# HHOLowCost.net
KiCad netlist of a schematic drawn in Altium Designer
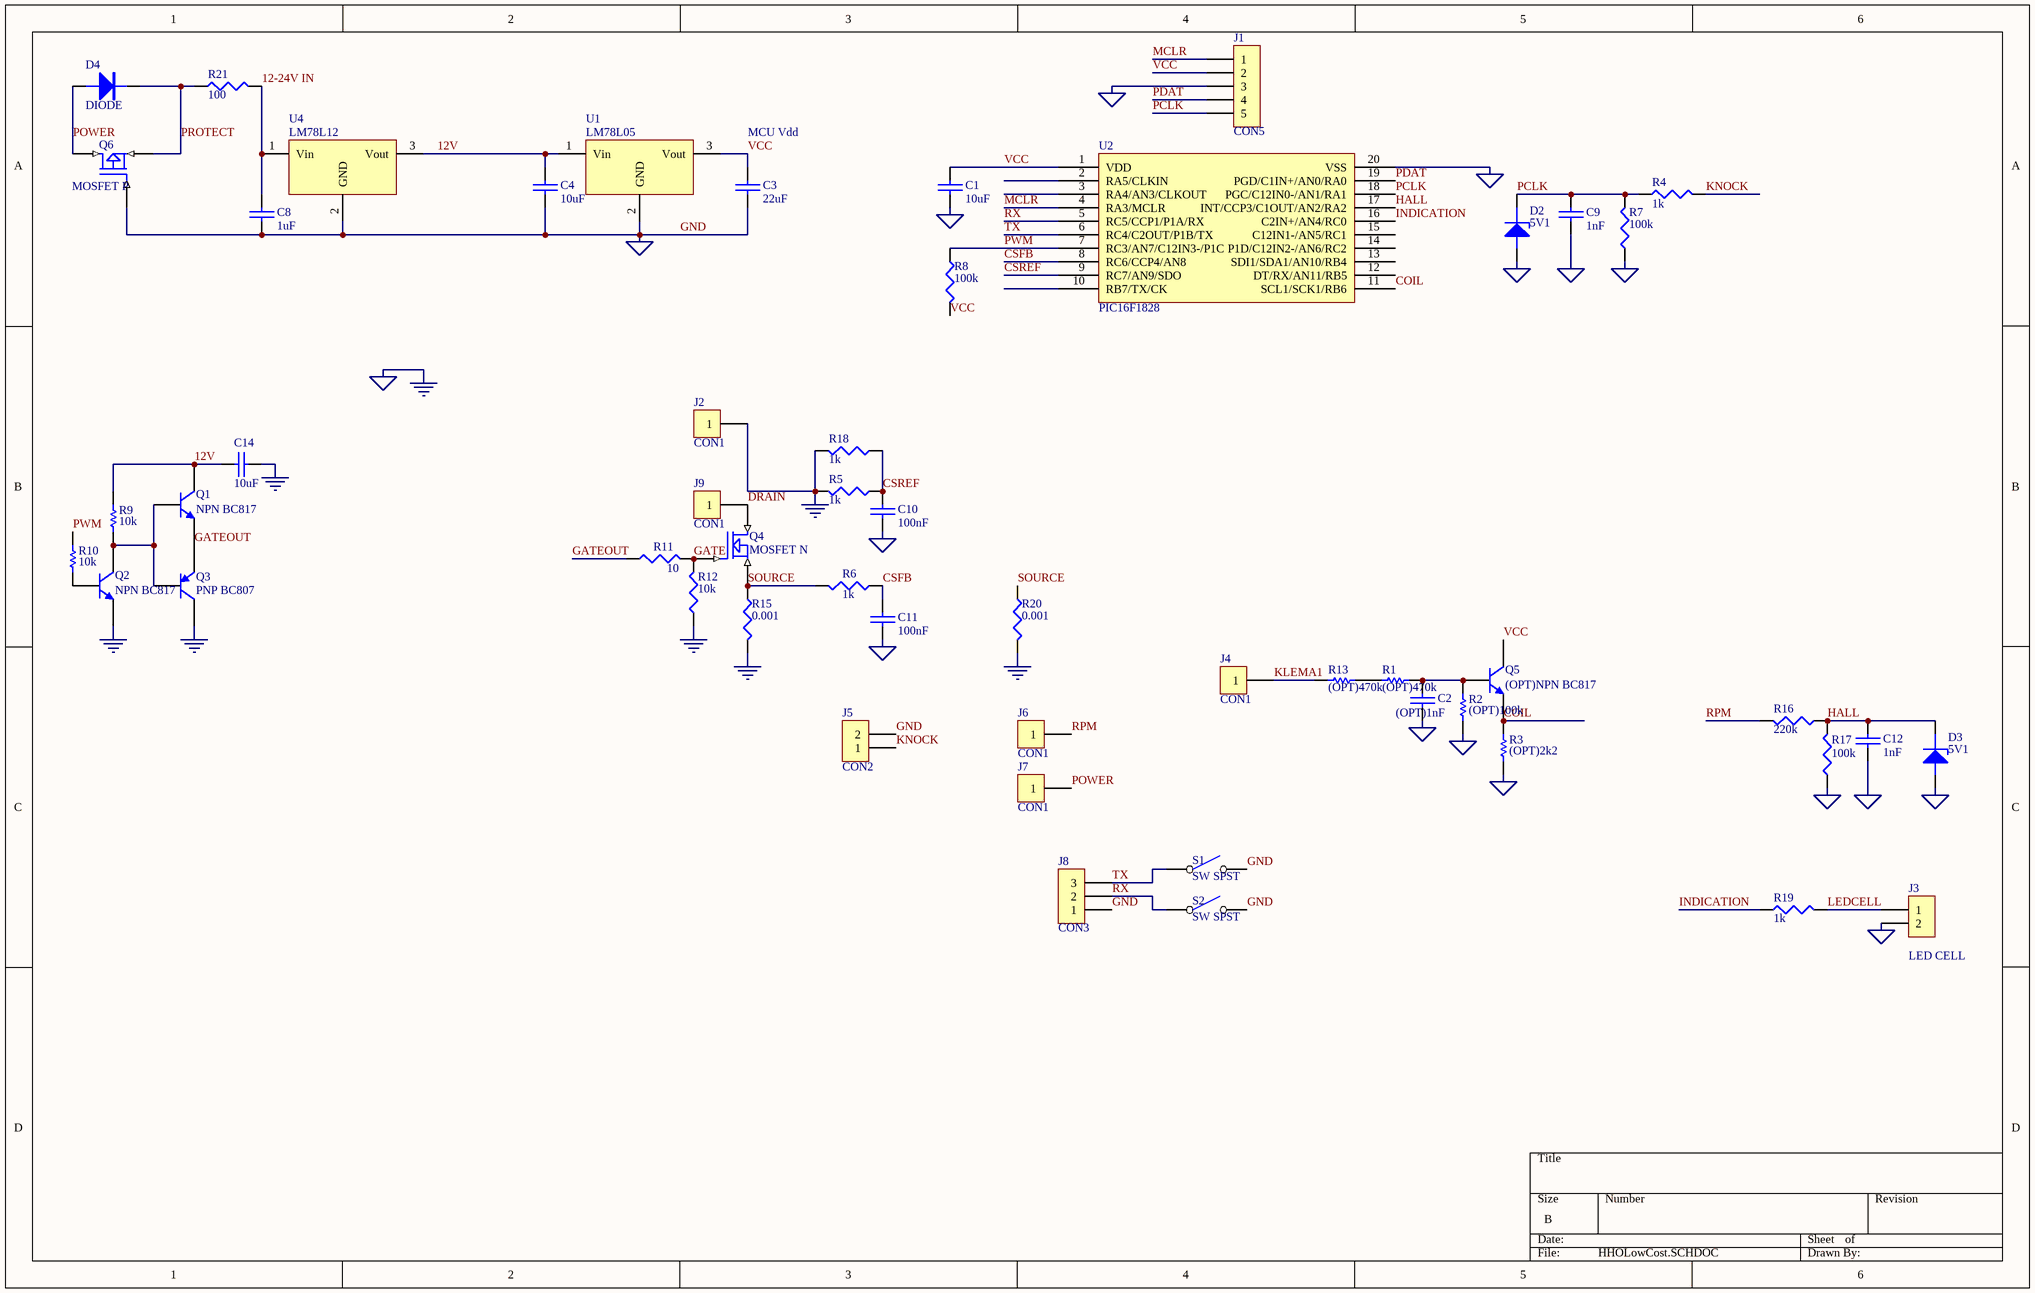
[diagram p0: HHOLowCost.SCHDOC]

(export (version "E")
  (design (tool "Eeschema 10.0.6"))
  (components
    (comp (ref "C1")
      (value "10uF")
      (footprint "0805")
      (description "Capacitor")
      (libsource (lib "*") (part "CAP"))
    )
    (comp (ref "C2")
      (value "(OPT)1nF")
      (footprint "0603 CAP")
      (description "Capacitor")
      (libsource (lib "*") (part "CAP"))
    )
    (comp (ref "C3")
      (value "22uF")
      (footprint "0805")
      (description "Capacitor")
      (libsource (lib "*") (part "CAP"))
    )
    (comp (ref "C4")
      (value "10uF")
      (footprint "0805")
      (description "Capacitor")
      (libsource (lib "*") (part "CAP"))
    )
    (comp (ref "C8")
      (value "1uF")
      (footprint "0805")
      (description "Capacitor")
      (libsource (lib "*") (part "CAP"))
    )
    (comp (ref "C9")
      (value "1nF")
      (footprint "0603 CAP")
      (description "Capacitor")
      (libsource (lib "*") (part "CAP"))
    )
    (comp (ref "C10")
      (value "100nF")
      (footprint "0603 CAP")
      (description "Capacitor")
      (libsource (lib "*") (part "CAP"))
    )
    (comp (ref "C11")
      (value "100nF")
      (footprint "0603 CAP")
      (description "Capacitor")
      (libsource (lib "*") (part "CAP"))
    )
    (comp (ref "C12")
      (value "1nF")
      (footprint "0603 CAP")
      (description "Capacitor")
      (libsource (lib "*") (part "CAP"))
    )
    (comp (ref "C14")
      (value "10uF")
      (footprint "0805")
      (description "Capacitor")
      (libsource (lib "*") (part "CAP"))
    )
    (comp (ref "D2")
      (value "5V1")
      (footprint "SOT-23 2 PIN")
      (description "Zener Diode")
      (libsource (lib "Miscellaneous Devices") (part "ZENER1"))
    )
    (comp (ref "D3")
      (value "5V1")
      (footprint "SOT-23 2 PIN")
      (description "Zener Diode")
      (libsource (lib "Miscellaneous Devices") (part "ZENER1"))
    )
    (comp (ref "D4")
      (value "DIODE")
      (footprint "SMA + SOT23")
      (description "Diode")
      (libsource (lib "Miscellaneous Devices") (part "DIODE"))
    )
    (comp (ref "J1")
      (value "CON5")
      (footprint "SIP5 - PGM")
      (description "Connector")
      (libsource (lib "Miscellaneous Devices") (part "CON5"))
    )
    (comp (ref "J2")
      (value "CON1")
      (footprint "HD 11mm 1P")
      (description "Connector")
      (libsource (lib "Miscellaneous Devices") (part "CON1"))
    )
    (comp (ref "J3")
      (value "LED CELL")
      (footprint "SIP2")
      (description "Connector")
      (libsource (lib "Miscellaneous Devices") (part "CON2"))
    )
    (comp (ref "J4")
      (value "CON1")
      (footprint "HD-351 1P")
      (description "Connector")
      (libsource (lib "Miscellaneous Devices") (part "CON1"))
    )
    (comp (ref "J5")
      (value "CON2")
      (footprint "HD-351 2P")
      (description "Connector")
      (libsource (lib "") (part "CON2_1"))
    )
    (comp (ref "J6")
      (value "CON1")
      (footprint "HD-351 1P")
      (description "Connector")
      (libsource (lib "Miscellaneous Devices") (part "CON1"))
    )
    (comp (ref "J7")
      (value "CON1")
      (footprint "HD-351 1P")
      (description "Connector")
      (libsource (lib "Miscellaneous Devices") (part "CON1"))
    )
    (comp (ref "J8")
      (value "CON3")
      (footprint "SIP3")
      (description "Connector")
      (libsource (lib "Miscellaneous Devices") (part "CON3"))
    )
    (comp (ref "J9")
      (value "CON1")
      (footprint "HD 11mm 1P")
      (description "Connector")
      (libsource (lib "Miscellaneous Devices") (part "CON1"))
    )
    (comp (ref "Q1")
      (value "NPN BC817")
      (footprint "SOT-23")
      (description "NPN Bipolar Transistor")
      (fields
        (field (name "MANUFACTURER") "Generic Components")
        (field (name "PUBLISHER") "Altium Hobart Technology Centre")
      )
      (libsource (lib "Miscellaneous Devices") (part "NPN"))
    )
    (comp (ref "Q2")
      (value "NPN BC817")
      (footprint "SOT-23")
      (description "NPN Bipolar Transistor")
      (fields
        (field (name "MANUFACTURER") "Generic Components")
        (field (name "PUBLISHER") "Altium Hobart Technology Centre")
      )
      (libsource (lib "Miscellaneous Devices") (part "NPN"))
    )
    (comp (ref "Q3")
      (value "PNP BC807")
      (footprint "sot-23")
      (description "PNP Bipolar Transistor")
      (fields
        (field (name "MANUFACTURER") "Generic Components")
        (field (name "PUBLISHER") "Altium Hobart Technology Centre")
      )
      (libsource (lib "Miscellaneous Devices") (part "PNP"))
    )
    (comp (ref "Q4")
      (value "MOSFET N")
      (footprint "D2-Pack - 7")
      (libsource (lib "Miscellaneous Devices") (part "MOSFET N"))
    )
    (comp (ref "Q5")
      (value "(OPT)NPN BC817")
      (footprint "SOT-23")
      (description "NPN Bipolar Transistor")
      (fields
        (field (name "MANUFACTURER") "Generic Components")
        (field (name "PUBLISHER") "Altium Hobart Technology Centre")
      )
      (libsource (lib "Miscellaneous Devices") (part "NPN"))
    )
    (comp (ref "Q6")
      (value "MOSFET P")
      (footprint "SOT-23")
      (libsource (lib "Miscellaneous Devices") (part "MOSFET P"))
    )
    (comp (ref "R1")
      (value "(OPT)470k")
      (footprint "0805")
      (description "Resistor")
      (fields
        (field (name "MANUFACTURER") "Generic Components")
        (field (name "PUBLISHER") "Altium Hobart Technology Centre")
      )
      (libsource (lib "Miscellaneous Devices") (part "Res1"))
    )
    (comp (ref "R2")
      (value "(OPT)100k")
      (footprint "0603")
      (description "Resistor")
      (fields
        (field (name "MANUFACTURER") "Generic Components")
        (field (name "PUBLISHER") "Altium Hobart Technology Centre")
      )
      (libsource (lib "Miscellaneous Devices") (part "Res1"))
    )
    (comp (ref "R3")
      (value "(OPT)2k2")
      (footprint "0603")
      (description "Resistor")
      (fields
        (field (name "MANUFACTURER") "Generic Components")
        (field (name "PUBLISHER") "Altium Hobart Technology Centre")
      )
      (libsource (lib "Miscellaneous Devices") (part "Res1"))
    )
    (comp (ref "R4")
      (value "1k")
      (footprint "0603 RES")
      (libsource (lib "Miscellaneous Devices") (part "RES1"))
    )
    (comp (ref "R5")
      (value "1k")
      (footprint "0603 RES")
      (libsource (lib "Miscellaneous Devices") (part "RES1"))
    )
    (comp (ref "R6")
      (value "1k")
      (footprint "0603 RES")
      (libsource (lib "Miscellaneous Devices") (part "RES1"))
    )
    (comp (ref "R7")
      (value "100k")
      (footprint "0603 RES")
      (libsource (lib "Miscellaneous Devices") (part "RES1"))
    )
    (comp (ref "R8")
      (value "100k")
      (footprint "0603 RES")
      (libsource (lib "Miscellaneous Devices") (part "RES1"))
    )
    (comp (ref "R9")
      (value "10k")
      (footprint "0603")
      (description "Resistor")
      (fields
        (field (name "MANUFACTURER") "Generic Components")
        (field (name "PUBLISHER") "Altium Hobart Technology Centre")
      )
      (libsource (lib "Miscellaneous Devices") (part "Res1"))
    )
    (comp (ref "R10")
      (value "10k")
      (footprint "0603")
      (description "Resistor")
      (fields
        (field (name "MANUFACTURER") "Generic Components")
        (field (name "PUBLISHER") "Altium Hobart Technology Centre")
      )
      (libsource (lib "Miscellaneous Devices") (part "Res1"))
    )
    (comp (ref "R11")
      (value "10")
      (footprint "0603 RES")
      (libsource (lib "Miscellaneous Devices") (part "RES1"))
    )
    (comp (ref "R12")
      (value "10k")
      (footprint "0603 RES")
      (libsource (lib "Miscellaneous Devices") (part "RES1"))
    )
    (comp (ref "R13")
      (value "(OPT)470k")
      (footprint "0805")
      (description "Resistor")
      (fields
        (field (name "MANUFACTURER") "Generic Components")
        (field (name "PUBLISHER") "Altium Hobart Technology Centre")
      )
      (libsource (lib "Miscellaneous Devices") (part "Res1"))
    )
    (comp (ref "R15")
      (value "0.001")
      (footprint "2512")
      (libsource (lib "Miscellaneous Devices") (part "RES1"))
    )
    (comp (ref "R16")
      (value "220k")
      (footprint "0603 RES")
      (libsource (lib "Miscellaneous Devices") (part "RES1"))
    )
    (comp (ref "R17")
      (value "100k")
      (footprint "0603 RES")
      (libsource (lib "Miscellaneous Devices") (part "RES1"))
    )
    (comp (ref "R18")
      (value "1k")
      (footprint "0603 RES")
      (libsource (lib "Miscellaneous Devices") (part "RES1"))
    )
    (comp (ref "R19")
      (value "1k")
      (footprint "0603 RES")
      (libsource (lib "Miscellaneous Devices") (part "RES1"))
    )
    (comp (ref "R20")
      (value "0.001")
      (footprint "1225")
      (libsource (lib "Miscellaneous Devices") (part "RES1"))
    )
    (comp (ref "R21")
      (value "100")
      (footprint "0805")
      (libsource (lib "Miscellaneous Devices") (part "RES1"))
    )
    (comp (ref "S1")
      (value "SW SPST")
      (footprint "TactBut")
      (libsource (lib "Miscellaneous Devices") (part "SW SPST"))
    )
    (comp (ref "S2")
      (value "SW SPST")
      (footprint "TactBut")
      (libsource (lib "Miscellaneous Devices") (part "SW SPST"))
    )
    (comp (ref "U1") (value "LM78L05") (footprint "SO-8 VOLTREG") (libsource (lib "*") (part "VOLTREG")))
    (comp (ref "U2")
      (value "PIC16F1828")
      (footprint "SOIC20WIDE")
      (description "Microchip Microcontroller")
      (libsource (lib "MCU") (part "PIC16F1828"))
    )
    (comp (ref "U4") (value "LM78L12") (footprint "SO-8 VOLTREG") (libsource (lib "*") (part "VOLTREG")))
  )
  (nets
    (net (code "1") (name "/12-24V IN") (class "Default")
      (node (ref "C8") (pin "1") (pinfunction "1_1") (pintype "passive"))
      (node (ref "R21") (pin "2") (pinfunction "2_2") (pintype "passive"))
      (node (ref "U4") (pin "1") (pinfunction "Vin_1") (pintype "passive"))
    )
    (net (code "2") (name "/12V") (class "Default")
      (node (ref "C14") (pin "2") (pinfunction "2_2") (pintype "passive"))
      (node (ref "C4") (pin "1") (pinfunction "1_1") (pintype "passive"))
      (node (ref "Q1") (pin "2") (pinfunction "C_2") (pintype "passive"))
      (node (ref "R9") (pin "1") (pinfunction "1_1") (pintype "passive"))
      (node (ref "U1") (pin "1") (pinfunction "Vin_1") (pintype "passive"))
      (node (ref "U4") (pin "3") (pinfunction "Vout_3") (pintype "passive"))
    )
    (net (code "3") (name "/COIL") (class "Default")
      (node (ref "Q5") (pin "3") (pinfunction "E_3") (pintype "passive"))
      (node (ref "R3") (pin "1") (pinfunction "1_1") (pintype "passive"))
      (node (ref "U2") (pin "11") (pinfunction "SCL1/SCK1/RB6_11") (pintype "passive"))
    )
    (net (code "4") (name "/CSFB") (class "Default")
      (node (ref "C11") (pin "1") (pinfunction "1_1") (pintype "passive"))
      (node (ref "R6") (pin "1") (pinfunction "1_1") (pintype "passive"))
      (node (ref "U2") (pin "8") (pinfunction "RC6/CCP4/AN8_8") (pintype "passive"))
    )
    (net (code "5") (name "/CSREF") (class "Default")
      (node (ref "C10") (pin "1") (pinfunction "1_1") (pintype "passive"))
      (node (ref "R18") (pin "1") (pinfunction "1_1") (pintype "passive"))
      (node (ref "R5") (pin "1") (pinfunction "1_1") (pintype "passive"))
      (node (ref "U2") (pin "9") (pinfunction "RC7/AN9/SDO_9") (pintype "passive"))
    )
    (net (code "6") (name "/DRAIN") (class "Default")
      (node (ref "J9") (pin "1") (pinfunction "1_1") (pintype "passive"))
      (node (ref "Q4") (pin "2") (pinfunction "D_2") (pintype "input"))
    )
    (net (code "7") (name "/GATE") (class "Default")
      (node (ref "Q4") (pin "1") (pinfunction "G_1") (pintype "input"))
      (node (ref "R11") (pin "2") (pinfunction "2_2") (pintype "passive"))
      (node (ref "R12") (pin "2") (pinfunction "2_2") (pintype "passive"))
    )
    (net (code "8") (name "/GATEOUT") (class "Default")
      (node (ref "Q1") (pin "3") (pinfunction "E_3") (pintype "passive"))
      (node (ref "Q3") (pin "3") (pinfunction "E_3") (pintype "passive"))
      (node (ref "R11") (pin "1") (pinfunction "1_1") (pintype "passive"))
    )
    (net (code "9") (name "/HALL") (class "Default")
      (node (ref "C12") (pin "1") (pinfunction "1_1") (pintype "passive"))
      (node (ref "D3") (pin "2") (pinfunction "K_2") (pintype "passive"))
      (node (ref "R16") (pin "1") (pinfunction "1_1") (pintype "passive"))
      (node (ref "R17") (pin "2") (pinfunction "2_2") (pintype "passive"))
      (node (ref "U2") (pin "17") (pinfunction "INT/CCP3/C1OUT/AN2/RA2_17") (pintype "passive"))
    )
    (net (code "10") (name "/INDICATION") (class "Default")
      (node (ref "R19") (pin "1") (pinfunction "1_1") (pintype "passive"))
      (node (ref "U2") (pin "16") (pinfunction "C2IN+/AN4/RC0_16") (pintype "passive"))
    )
    (net (code "11") (name "/KLEMA1") (class "Default")
      (node (ref "J4") (pin "1") (pinfunction "1_1") (pintype "passive"))
      (node (ref "R13") (pin "2") (pinfunction "2_2") (pintype "passive"))
    )
    (net (code "12") (name "/KNOCK") (class "Default")
      (node (ref "J5") (pin "1") (pinfunction "1_1") (pintype "passive"))
      (node (ref "R4") (pin "2") (pinfunction "2_2") (pintype "passive"))
    )
    (net (code "13") (name "/LEDCELL") (class "Default")
      (node (ref "J3") (pin "1") (pinfunction "1_1") (pintype "passive"))
      (node (ref "R19") (pin "2") (pinfunction "2_2") (pintype "passive"))
    )
    (net (code "14") (name "/MCLR") (class "Default")
      (node (ref "J1") (pin "1") (pinfunction "1_1") (pintype "passive"))
      (node (ref "U2") (pin "4") (pinfunction "RA3/MCLR_4") (pintype "passive"))
    )
    (net (code "15") (name "/PCLK") (class "Default")
      (node (ref "C9") (pin "1") (pinfunction "1_1") (pintype "passive"))
      (node (ref "D2") (pin "2") (pinfunction "K_2") (pintype "passive"))
      (node (ref "J1") (pin "5") (pinfunction "5_5") (pintype "passive"))
      (node (ref "R4") (pin "1") (pinfunction "1_1") (pintype "passive"))
      (node (ref "R7") (pin "2") (pinfunction "2_2") (pintype "passive"))
      (node (ref "U2") (pin "18") (pinfunction "PGC/C12IN0-/AN1/RA1_18") (pintype "passive"))
    )
    (net (code "16") (name "/PDAT") (class "Default")
      (node (ref "J1") (pin "4") (pinfunction "4_4") (pintype "passive"))
      (node (ref "U2") (pin "19") (pinfunction "PGD/C1IN+/AN0/RA0_19") (pintype "passive"))
    )
    (net (code "17") (name "/POWER") (class "Default")
      (node (ref "D4") (pin "A") (pinfunction "A_A") (pintype "passive"))
      (node (ref "J7") (pin "1") (pinfunction "1_1") (pintype "passive"))
      (node (ref "Q6") (pin "2") (pinfunction "D_2") (pintype "input"))
    )
    (net (code "18") (name "/PROTECT") (class "Default")
      (node (ref "D4") (pin "K") (pinfunction "K_K") (pintype "passive"))
      (node (ref "Q6") (pin "3") (pinfunction "S_3") (pintype "input"))
      (node (ref "R21") (pin "1") (pinfunction "1_1") (pintype "passive"))
    )
    (net (code "19") (name "/PWM") (class "Default")
      (node (ref "R10") (pin "1") (pinfunction "1_1") (pintype "passive"))
      (node (ref "R8") (pin "1") (pinfunction "1_1") (pintype "passive"))
      (node (ref "U2") (pin "7") (pinfunction "RC3/AN7/C12IN3-/P1C_7") (pintype "passive"))
    )
    (net (code "20") (name "/RPM") (class "Default")
      (node (ref "J6") (pin "1") (pinfunction "1_1") (pintype "passive"))
      (node (ref "R16") (pin "2") (pinfunction "2_2") (pintype "passive"))
    )
    (net (code "21") (name "/RX") (class "Default")
      (node (ref "J8") (pin "2") (pinfunction "2_2") (pintype "passive"))
      (node (ref "S2") (pin "1") (pinfunction "COMMON_1") (pintype "passive"))
      (node (ref "U2") (pin "5") (pinfunction "RC5/CCP1/P1A/RX_5") (pintype "passive"))
    )
    (net (code "22") (name "/SOURCE") (class "Default")
      (node (ref "Q4") (pin "3") (pinfunction "S_3") (pintype "input"))
      (node (ref "R15") (pin "1") (pinfunction "1_1") (pintype "passive"))
      (node (ref "R20") (pin "1") (pinfunction "1_1") (pintype "passive"))
      (node (ref "R6") (pin "2") (pinfunction "2_2") (pintype "passive"))
    )
    (net (code "23") (name "/TX") (class "Default")
      (node (ref "J8") (pin "3") (pinfunction "3_3") (pintype "passive"))
      (node (ref "S1") (pin "1") (pinfunction "COMMON_1") (pintype "passive"))
      (node (ref "U2") (pin "6") (pinfunction "RC4/C2OUT/P1B/TX_6") (pintype "passive"))
    )
    (net (code "24") (name "/VCC") (class "Default")
      (node (ref "C1") (pin "1") (pinfunction "1_1") (pintype "passive"))
      (node (ref "C3") (pin "1") (pinfunction "1_1") (pintype "passive"))
      (node (ref "J1") (pin "2") (pinfunction "2_2") (pintype "passive"))
      (node (ref "Q5") (pin "2") (pinfunction "C_2") (pintype "passive"))
      (node (ref "R8") (pin "2") (pinfunction "2_2") (pintype "passive"))
      (node (ref "U1") (pin "3") (pinfunction "Vout_3") (pintype "passive"))
      (node (ref "U2") (pin "1") (pinfunction "VDD_1") (pintype "passive"))
    )
    (net (code "25") (name "Net-(Q1-B)") (class "Default")
      (node (ref "Q1") (pin "1") (pinfunction "B_1") (pintype "passive"))
      (node (ref "Q2") (pin "2") (pinfunction "C_2") (pintype "passive"))
      (node (ref "Q3") (pin "1") (pinfunction "B_1") (pintype "passive"))
      (node (ref "R9") (pin "2") (pinfunction "2_2") (pintype "passive"))
    )
    (net (code "26") (name "Net-(Q2-B)") (class "Default")
      (node (ref "Q2") (pin "1") (pinfunction "B_1") (pintype "passive"))
      (node (ref "R10") (pin "2") (pinfunction "2_2") (pintype "passive"))
    )
    (net (code "27") (name "Net-(Q5-B)") (class "Default")
      (node (ref "C2") (pin "1") (pinfunction "1_1") (pintype "passive"))
      (node (ref "Q5") (pin "1") (pinfunction "B_1") (pintype "passive"))
      (node (ref "R1") (pin "1") (pinfunction "1_1") (pintype "passive"))
      (node (ref "R2") (pin "1") (pinfunction "1_1") (pintype "passive"))
    )
    (net (code "28") (name "Net-(R1-Pad2)") (class "Default")
      (node (ref "R1") (pin "2") (pinfunction "2_2") (pintype "passive"))
      (node (ref "R13") (pin "1") (pinfunction "1_1") (pintype "passive"))
    )
    (net (code "29") (name "PGND") (class "Default")
      (node (ref "C1") (pin "2") (pinfunction "2_2") (pintype "passive"))
      (node (ref "C10") (pin "2") (pinfunction "2_2") (pintype "passive"))
      (node (ref "C11") (pin "2") (pinfunction "2_2") (pintype "passive"))
      (node (ref "C12") (pin "2") (pinfunction "2_2") (pintype "passive"))
      (node (ref "C14") (pin "1") (pinfunction "1_1") (pintype "passive"))
      (node (ref "C2") (pin "2") (pinfunction "2_2") (pintype "passive"))
      (node (ref "C3") (pin "2") (pinfunction "2_2") (pintype "passive"))
      (node (ref "C4") (pin "2") (pinfunction "2_2") (pintype "passive"))
      (node (ref "C8") (pin "2") (pinfunction "2_2") (pintype "passive"))
      (node (ref "C9") (pin "2") (pinfunction "2_2") (pintype "passive"))
      (node (ref "D2") (pin "1") (pinfunction "A_1") (pintype "passive"))
      (node (ref "D3") (pin "1") (pinfunction "A_1") (pintype "passive"))
      (node (ref "J1") (pin "3") (pinfunction "3_3") (pintype "passive"))
      (node (ref "J2") (pin "1") (pinfunction "1_1") (pintype "passive"))
      (node (ref "J3") (pin "2") (pinfunction "2_2") (pintype "passive"))
      (node (ref "J5") (pin "2") (pinfunction "2_2") (pintype "passive"))
      (node (ref "J8") (pin "1") (pinfunction "1_1") (pintype "passive"))
      (node (ref "Q2") (pin "3") (pinfunction "E_3") (pintype "passive"))
      (node (ref "Q3") (pin "2") (pinfunction "C_2") (pintype "passive"))
      (node (ref "Q6") (pin "1") (pinfunction "G_1") (pintype "input"))
      (node (ref "R12") (pin "1") (pinfunction "1_1") (pintype "passive"))
      (node (ref "R15") (pin "2") (pinfunction "2_2") (pintype "passive"))
      (node (ref "R17") (pin "1") (pinfunction "1_1") (pintype "passive"))
      (node (ref "R18") (pin "2") (pinfunction "2_2") (pintype "passive"))
      (node (ref "R2") (pin "2") (pinfunction "2_2") (pintype "passive"))
      (node (ref "R20") (pin "2") (pinfunction "2_2") (pintype "passive"))
      (node (ref "R3") (pin "2") (pinfunction "2_2") (pintype "passive"))
      (node (ref "R5") (pin "2") (pinfunction "2_2") (pintype "passive"))
      (node (ref "R7") (pin "1") (pinfunction "1_1") (pintype "passive"))
      (node (ref "S1") (pin "2") (pinfunction "NO_2") (pintype "passive"))
      (node (ref "S2") (pin "2") (pinfunction "NO_2") (pintype "passive"))
      (node (ref "U1") (pin "2") (pinfunction "GND_2") (pintype "passive"))
      (node (ref "U2") (pin "20") (pinfunction "VSS_20") (pintype "passive"))
      (node (ref "U4") (pin "2") (pinfunction "GND_2") (pintype "passive"))
    )
    (net (code "30") (name "unconnected-(U2-C12IN1-{slash}AN5{slash}RC1-Pad15)") (class "Default")
      (node (ref "U2") (pin "15") (pinfunction "C12IN1-/AN5/RC1_15") (pintype "passive"))
    )
    (net (code "31") (name "unconnected-(U2-DT{slash}RX{slash}AN11{slash}RB5-Pad12)") (class "Default")
      (node (ref "U2") (pin "12") (pinfunction "DT/RX/AN11/RB5_12") (pintype "passive"))
    )
    (net (code "32") (name "unconnected-(U2-P1D{slash}C12IN2-{slash}AN6{slash}RC2-Pad14)") (class "Default")
      (node (ref "U2") (pin "14") (pinfunction "P1D/C12IN2-/AN6/RC2_14") (pintype "passive"))
    )
    (net (code "33") (name "unconnected-(U2-RA4{slash}AN3{slash}CLKOUT-Pad3)") (class "Default")
      (node (ref "U2") (pin "3") (pinfunction "RA4/AN3/CLKOUT_3") (pintype "passive"))
    )
    (net (code "34") (name "unconnected-(U2-RA5{slash}CLKIN-Pad2)") (class "Default")
      (node (ref "U2") (pin "2") (pinfunction "RA5/CLKIN_2") (pintype "passive"))
    )
    (net (code "35") (name "unconnected-(U2-RB7{slash}TX{slash}CK-Pad10)") (class "Default")
      (node (ref "U2") (pin "10") (pinfunction "RB7/TX/CK_10") (pintype "passive"))
    )
    (net (code "36") (name "unconnected-(U2-SDI1{slash}SDA1{slash}AN10{slash}RB4-Pad13)") (class "Default")
      (node (ref "U2") (pin "13") (pinfunction "SDI1/SDA1/AN10/RB4_13") (pintype "passive"))
    )
  )
)
